# receiver.net
KiCad netlist of a schematic drawn in EAGLE
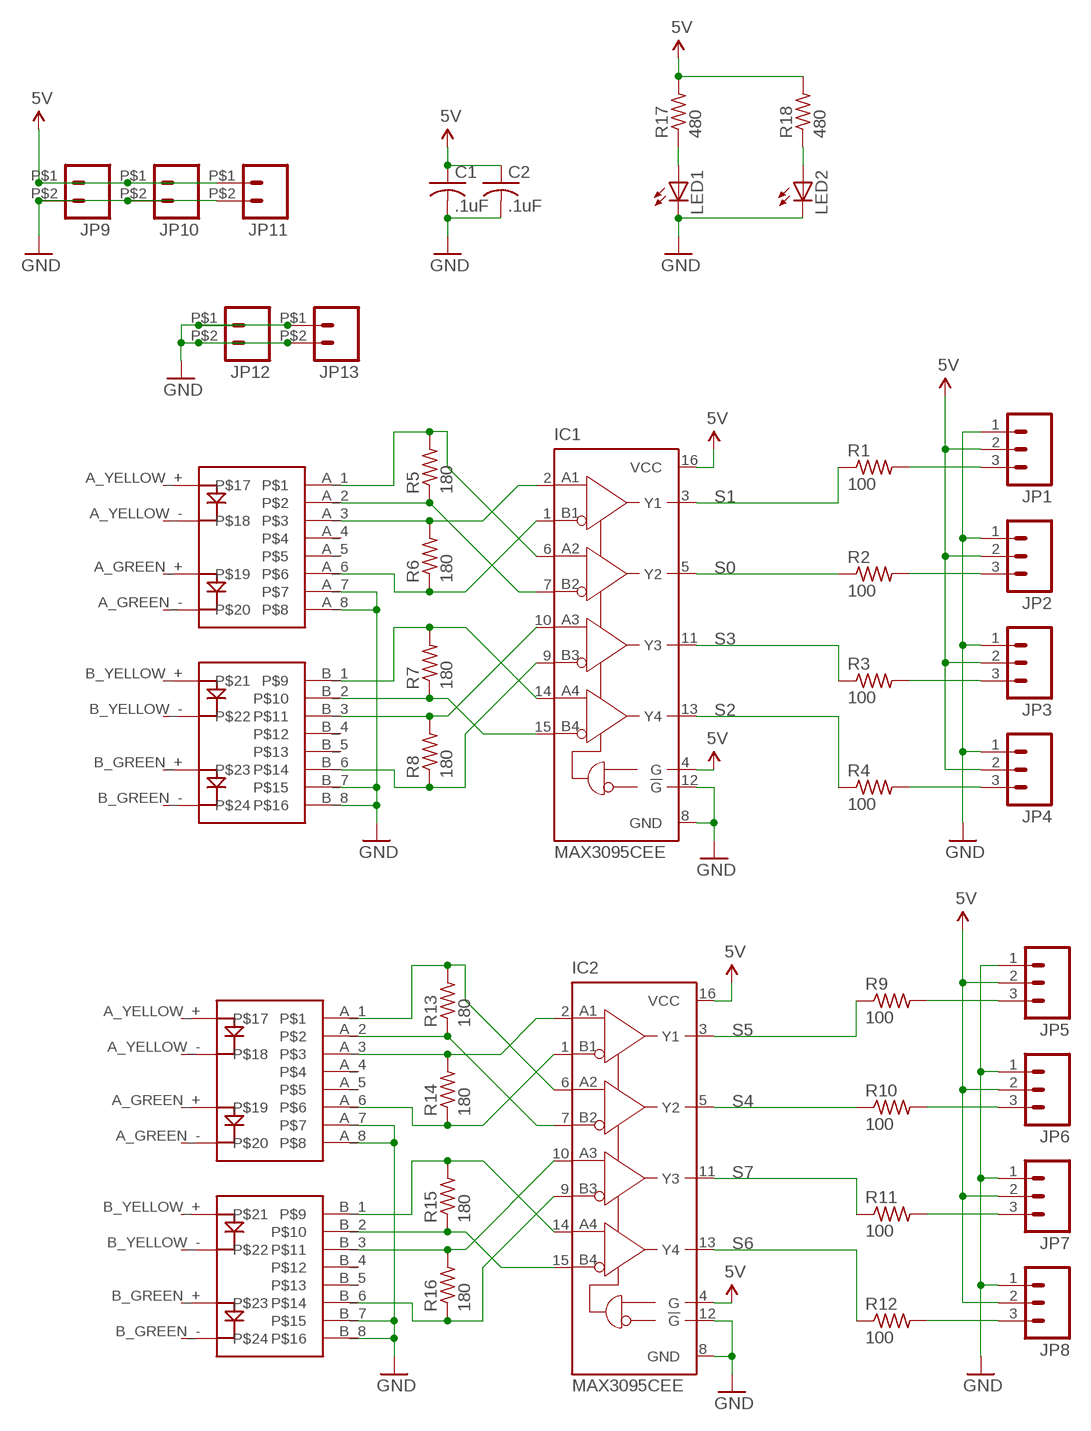
[diagram p0: schematic, sheet 1]

(export (version "E")
  (design (tool "Eeschema 10.0.6"))
  (components
    (comp (ref "C1")
      (value ".1uF")
      (footprint "eagle-import:C0603")
      (libsource (lib "eagle-import") (part "C-USC0603"))
    )
    (comp (ref "C2")
      (value ".1uF")
      (footprint "eagle-import:C0603")
      (libsource (lib "eagle-import") (part "C-USC0603"))
    )
    (comp (ref "IC1")
      (value "MAX3095CEE")
      (footprint "eagle-import:QSOP16")
      (fields (field (name "MPN") "MAX3095CEE+"))
      (libsource (lib "eagle-import") (part "MAX309EE5C"))
    )
    (comp (ref "IC2")
      (value "MAX3095CEE")
      (footprint "eagle-import:QSOP16")
      (fields (field (name "MPN") "MAX3095CEE+"))
      (libsource (lib "eagle-import") (part "MAX309EE5C"))
    )
    (comp (ref "JP1")
      (value "M03-SCREW-5MM")
      (footprint "eagle-import:SCREWTERMINAL-5MM-3")
      (libsource (lib "eagle-import") (part "M03-SCREW-5MM"))
    )
    (comp (ref "JP2")
      (value "M03-SCREW-5MM")
      (footprint "eagle-import:SCREWTERMINAL-5MM-3")
      (libsource (lib "eagle-import") (part "M03-SCREW-5MM"))
    )
    (comp (ref "JP3")
      (value "M03-SCREW-5MM")
      (footprint "eagle-import:SCREWTERMINAL-5MM-3")
      (libsource (lib "eagle-import") (part "M03-SCREW-5MM"))
    )
    (comp (ref "JP4")
      (value "M03-SCREW-5MM")
      (footprint "eagle-import:SCREWTERMINAL-5MM-3")
      (libsource (lib "eagle-import") (part "M03-SCREW-5MM"))
    )
    (comp (ref "JP5")
      (value "M03-SCREW-5MM")
      (footprint "eagle-import:SCREWTERMINAL-5MM-3")
      (libsource (lib "eagle-import") (part "M03-SCREW-5MM"))
    )
    (comp (ref "JP6")
      (value "M03-SCREW-5MM")
      (footprint "eagle-import:SCREWTERMINAL-5MM-3")
      (libsource (lib "eagle-import") (part "M03-SCREW-5MM"))
    )
    (comp (ref "JP7")
      (value "M03-SCREW-5MM")
      (footprint "eagle-import:SCREWTERMINAL-5MM-3")
      (libsource (lib "eagle-import") (part "M03-SCREW-5MM"))
    )
    (comp (ref "JP8")
      (value "M03-SCREW-5MM")
      (footprint "eagle-import:SCREWTERMINAL-5MM-3")
      (libsource (lib "eagle-import") (part "M03-SCREW-5MM"))
    )
    (comp (ref "JP9")
      (value "M026.35MM")
      (footprint "eagle-import:SCREWTERMINAL-6.35MM-2")
      (libsource (lib "eagle-import") (part "M026.35MM"))
    )
    (comp (ref "JP10")
      (value "M026.35MM")
      (footprint "eagle-import:SCREWTERMINAL-6.35MM-2")
      (libsource (lib "eagle-import") (part "M026.35MM"))
    )
    (comp (ref "JP11")
      (value "M026.35MM")
      (footprint "eagle-import:SCREWTERMINAL-6.35MM-2")
      (libsource (lib "eagle-import") (part "M026.35MM"))
    )
    (comp (ref "JP12")
      (value "M026.35MM")
      (footprint "eagle-import:SCREWTERMINAL-6.35MM-2")
      (libsource (lib "eagle-import") (part "M026.35MM"))
    )
    (comp (ref "JP13")
      (value "M026.35MM")
      (footprint "eagle-import:SCREWTERMINAL-6.35MM-2")
      (libsource (lib "eagle-import") (part "M026.35MM"))
    )
    (comp (ref "LED1")
      (value "LEDCHIPLED_0805")
      (footprint "eagle-import:CHIPLED_0805")
      (libsource (lib "eagle-import") (part "LEDCHIPLED_0805"))
    )
    (comp (ref "LED2")
      (value "LEDCHIPLED_0805")
      (footprint "eagle-import:CHIPLED_0805")
      (libsource (lib "eagle-import") (part "LEDCHIPLED_0805"))
    )
    (comp (ref "R1")
      (value "100")
      (footprint "eagle-import:R0603")
      (libsource (lib "eagle-import") (part "R-US_R0603"))
    )
    (comp (ref "R2")
      (value "100")
      (footprint "eagle-import:R0603")
      (libsource (lib "eagle-import") (part "R-US_R0603"))
    )
    (comp (ref "R3")
      (value "100")
      (footprint "eagle-import:R0603")
      (libsource (lib "eagle-import") (part "R-US_R0603"))
    )
    (comp (ref "R4")
      (value "100")
      (footprint "eagle-import:R0603")
      (libsource (lib "eagle-import") (part "R-US_R0603"))
    )
    (comp (ref "R5")
      (value "180")
      (footprint "eagle-import:R0603")
      (libsource (lib "eagle-import") (part "R-US_R0603"))
    )
    (comp (ref "R6")
      (value "180")
      (footprint "eagle-import:R0603")
      (libsource (lib "eagle-import") (part "R-US_R0603"))
    )
    (comp (ref "R7")
      (value "180")
      (footprint "eagle-import:R0603")
      (libsource (lib "eagle-import") (part "R-US_R0603"))
    )
    (comp (ref "R8")
      (value "180")
      (footprint "eagle-import:R0603")
      (libsource (lib "eagle-import") (part "R-US_R0603"))
    )
    (comp (ref "R9")
      (value "100")
      (footprint "eagle-import:R0603")
      (libsource (lib "eagle-import") (part "R-US_R0603"))
    )
    (comp (ref "R10")
      (value "100")
      (footprint "eagle-import:R0603")
      (libsource (lib "eagle-import") (part "R-US_R0603"))
    )
    (comp (ref "R11")
      (value "100")
      (footprint "eagle-import:R0603")
      (libsource (lib "eagle-import") (part "R-US_R0603"))
    )
    (comp (ref "R12")
      (value "100")
      (footprint "eagle-import:R0603")
      (libsource (lib "eagle-import") (part "R-US_R0603"))
    )
    (comp (ref "R13")
      (value "180")
      (footprint "eagle-import:R0603")
      (libsource (lib "eagle-import") (part "R-US_R0603"))
    )
    (comp (ref "R14")
      (value "180")
      (footprint "eagle-import:R0603")
      (libsource (lib "eagle-import") (part "R-US_R0603"))
    )
    (comp (ref "R15")
      (value "180")
      (footprint "eagle-import:R0603")
      (libsource (lib "eagle-import") (part "R-US_R0603"))
    )
    (comp (ref "R16")
      (value "180")
      (footprint "eagle-import:R0603")
      (libsource (lib "eagle-import") (part "R-US_R0603"))
    )
    (comp (ref "R17")
      (value "480")
      (footprint "eagle-import:R0603")
      (libsource (lib "eagle-import") (part "R-US_R0603"))
    )
    (comp (ref "R18")
      (value "480")
      (footprint "eagle-import:R0603")
      (libsource (lib "eagle-import") (part "R-US_R0603"))
    )
    (comp (ref "U$1")
      (value "RJ45_2X1")
      (footprint "eagle-import:RJ45_2X1")
      (libsource (lib "eagle-import") (part "RJ45_2X1"))
    )
    (comp (ref "U$2")
      (value "RJ45_2X1")
      (footprint "eagle-import:RJ45_2X1")
      (libsource (lib "eagle-import") (part "RJ45_2X1"))
    )
  )
  (nets
    (net (code "1") (name "/S0") (class "Default")
      (node (ref "IC1") (pin "5") (pinfunction "Y2_5") (pintype "output"))
      (node (ref "R2") (pin "1") (pinfunction "1_1") (pintype "passive"))
    )
    (net (code "2") (name "/S1") (class "Default")
      (node (ref "IC1") (pin "3") (pinfunction "Y1_3") (pintype "output"))
      (node (ref "R1") (pin "1") (pinfunction "1_1") (pintype "passive"))
    )
    (net (code "3") (name "/S2") (class "Default")
      (node (ref "IC1") (pin "13") (pinfunction "Y4_13") (pintype "output"))
      (node (ref "R4") (pin "1") (pinfunction "1_1") (pintype "passive"))
    )
    (net (code "4") (name "/S3") (class "Default")
      (node (ref "IC1") (pin "11") (pinfunction "Y3_11") (pintype "output"))
      (node (ref "R3") (pin "1") (pinfunction "1_1") (pintype "passive"))
    )
    (net (code "5") (name "/S4") (class "Default")
      (node (ref "IC2") (pin "5") (pinfunction "Y2_5") (pintype "output"))
      (node (ref "R10") (pin "1") (pinfunction "1_1") (pintype "passive"))
    )
    (net (code "6") (name "/S5") (class "Default")
      (node (ref "IC2") (pin "3") (pinfunction "Y1_3") (pintype "output"))
      (node (ref "R9") (pin "1") (pinfunction "1_1") (pintype "passive"))
    )
    (net (code "7") (name "/S6") (class "Default")
      (node (ref "IC2") (pin "13") (pinfunction "Y4_13") (pintype "output"))
      (node (ref "R12") (pin "1") (pinfunction "1_1") (pintype "passive"))
    )
    (net (code "8") (name "/S7") (class "Default")
      (node (ref "IC2") (pin "11") (pinfunction "Y3_11") (pintype "output"))
      (node (ref "R11") (pin "1") (pinfunction "1_1") (pintype "passive"))
    )
    (net (code "9") (name "5V") (class "Default")
      (node (ref "C1") (pin "1") (pinfunction "1_1") (pintype "passive"))
      (node (ref "C2") (pin "1") (pinfunction "1_1") (pintype "passive"))
      (node (ref "IC1") (pin "16") (pinfunction "VCC_16") (pintype "power_in"))
      (node (ref "IC1") (pin "4") (pinfunction "G_4") (pintype "input"))
      (node (ref "IC2") (pin "16") (pinfunction "VCC_16") (pintype "power_in"))
      (node (ref "IC2") (pin "4") (pinfunction "G_4") (pintype "input"))
      (node (ref "JP1") (pin "2") (pinfunction "2_2") (pintype "passive"))
      (node (ref "JP10") (pin "P$1") (pinfunction "1_P$1") (pintype "passive"))
      (node (ref "JP11") (pin "P$1") (pinfunction "1_P$1") (pintype "passive"))
      (node (ref "JP2") (pin "2") (pinfunction "2_2") (pintype "passive"))
      (node (ref "JP3") (pin "2") (pinfunction "2_2") (pintype "passive"))
      (node (ref "JP4") (pin "2") (pinfunction "2_2") (pintype "passive"))
      (node (ref "JP5") (pin "2") (pinfunction "2_2") (pintype "passive"))
      (node (ref "JP6") (pin "2") (pinfunction "2_2") (pintype "passive"))
      (node (ref "JP7") (pin "2") (pinfunction "2_2") (pintype "passive"))
      (node (ref "JP8") (pin "2") (pinfunction "2_2") (pintype "passive"))
      (node (ref "JP9") (pin "P$1") (pinfunction "1_P$1") (pintype "passive"))
      (node (ref "R17") (pin "2") (pinfunction "2_2") (pintype "passive"))
      (node (ref "R18") (pin "2") (pinfunction "2_2") (pintype "passive"))
    )
    (net (code "10") (name "GND") (class "Default")
      (node (ref "C1") (pin "2") (pinfunction "2_2") (pintype "passive"))
      (node (ref "C2") (pin "2") (pinfunction "2_2") (pintype "passive"))
      (node (ref "IC1") (pin "12") (pinfunction "~{G}_12") (pintype "input"))
      (node (ref "IC1") (pin "8") (pinfunction "GND_8") (pintype "power_in"))
      (node (ref "IC2") (pin "12") (pinfunction "~{G}_12") (pintype "input"))
      (node (ref "IC2") (pin "8") (pinfunction "GND_8") (pintype "power_in"))
      (node (ref "JP1") (pin "1") (pinfunction "1_1") (pintype "passive"))
      (node (ref "JP10") (pin "P$2") (pinfunction "2_P$2") (pintype "passive"))
      (node (ref "JP11") (pin "P$2") (pinfunction "2_P$2") (pintype "passive"))
      (node (ref "JP12") (pin "P$1") (pinfunction "1_P$1") (pintype "passive"))
      (node (ref "JP12") (pin "P$2") (pinfunction "2_P$2") (pintype "passive"))
      (node (ref "JP13") (pin "P$1") (pinfunction "1_P$1") (pintype "passive"))
      (node (ref "JP13") (pin "P$2") (pinfunction "2_P$2") (pintype "passive"))
      (node (ref "JP2") (pin "1") (pinfunction "1_1") (pintype "passive"))
      (node (ref "JP3") (pin "1") (pinfunction "1_1") (pintype "passive"))
      (node (ref "JP4") (pin "1") (pinfunction "1_1") (pintype "passive"))
      (node (ref "JP5") (pin "1") (pinfunction "1_1") (pintype "passive"))
      (node (ref "JP6") (pin "1") (pinfunction "1_1") (pintype "passive"))
      (node (ref "JP7") (pin "1") (pinfunction "1_1") (pintype "passive"))
      (node (ref "JP8") (pin "1") (pinfunction "1_1") (pintype "passive"))
      (node (ref "JP9") (pin "P$2") (pinfunction "2_P$2") (pintype "passive"))
      (node (ref "LED1") (pin "C") (pinfunction "C_C") (pintype "passive"))
      (node (ref "LED2") (pin "C") (pinfunction "C_C") (pintype "passive"))
      (node (ref "U$1") (pin "A_7") (pinfunction "P$7_A_7") (pintype "bidirectional"))
      (node (ref "U$1") (pin "A_8") (pinfunction "P$8_A_8") (pintype "bidirectional"))
      (node (ref "U$1") (pin "B_7") (pinfunction "P$15_B_7") (pintype "bidirectional"))
      (node (ref "U$1") (pin "B_8") (pinfunction "P$16_B_8") (pintype "bidirectional"))
      (node (ref "U$2") (pin "A_7") (pinfunction "P$7_A_7") (pintype "bidirectional"))
      (node (ref "U$2") (pin "A_8") (pinfunction "P$8_A_8") (pintype "bidirectional"))
      (node (ref "U$2") (pin "B_7") (pinfunction "P$15_B_7") (pintype "bidirectional"))
      (node (ref "U$2") (pin "B_8") (pinfunction "P$16_B_8") (pintype "bidirectional"))
    )
    (net (code "11") (name "Net-(IC1-A1)") (class "Default")
      (node (ref "IC1") (pin "2") (pinfunction "A1_2") (pintype "input"))
      (node (ref "R6") (pin "2") (pinfunction "2_2") (pintype "passive"))
      (node (ref "U$1") (pin "A_3") (pinfunction "P$3_A_3") (pintype "bidirectional"))
    )
    (net (code "12") (name "Net-(IC1-A2)") (class "Default")
      (node (ref "IC1") (pin "6") (pinfunction "A2_6") (pintype "input"))
      (node (ref "R5") (pin "2") (pinfunction "2_2") (pintype "passive"))
      (node (ref "U$1") (pin "A_1") (pinfunction "P$1_A_1") (pintype "bidirectional"))
    )
    (net (code "13") (name "Net-(IC1-A3)") (class "Default")
      (node (ref "IC1") (pin "10") (pinfunction "A3_10") (pintype "input"))
      (node (ref "R8") (pin "2") (pinfunction "2_2") (pintype "passive"))
      (node (ref "U$1") (pin "B_3") (pinfunction "P$11_B_3") (pintype "bidirectional"))
    )
    (net (code "14") (name "Net-(IC1-A4)") (class "Default")
      (node (ref "IC1") (pin "14") (pinfunction "A4_14") (pintype "input"))
      (node (ref "R7") (pin "2") (pinfunction "2_2") (pintype "passive"))
      (node (ref "U$1") (pin "B_1") (pinfunction "P$9_B_1") (pintype "bidirectional"))
    )
    (net (code "15") (name "Net-(IC1-B1)") (class "Default")
      (node (ref "IC1") (pin "1") (pinfunction "B1_1") (pintype "input"))
      (node (ref "R6") (pin "1") (pinfunction "1_1") (pintype "passive"))
      (node (ref "U$1") (pin "A_6") (pinfunction "P$6_A_6") (pintype "bidirectional"))
    )
    (net (code "16") (name "Net-(IC1-B2)") (class "Default")
      (node (ref "IC1") (pin "7") (pinfunction "B2_7") (pintype "input"))
      (node (ref "R5") (pin "1") (pinfunction "1_1") (pintype "passive"))
      (node (ref "U$1") (pin "A_2") (pinfunction "P$2_A_2") (pintype "bidirectional"))
    )
    (net (code "17") (name "Net-(IC1-B3)") (class "Default")
      (node (ref "IC1") (pin "9") (pinfunction "B3_9") (pintype "input"))
      (node (ref "R8") (pin "1") (pinfunction "1_1") (pintype "passive"))
      (node (ref "U$1") (pin "B_6") (pinfunction "P$14_B_6") (pintype "bidirectional"))
    )
    (net (code "18") (name "Net-(IC1-B4)") (class "Default")
      (node (ref "IC1") (pin "15") (pinfunction "B4_15") (pintype "input"))
      (node (ref "R7") (pin "1") (pinfunction "1_1") (pintype "passive"))
      (node (ref "U$1") (pin "B_2") (pinfunction "P$10_B_2") (pintype "bidirectional"))
    )
    (net (code "19") (name "Net-(IC2-A1)") (class "Default")
      (node (ref "IC2") (pin "2") (pinfunction "A1_2") (pintype "input"))
      (node (ref "R14") (pin "2") (pinfunction "2_2") (pintype "passive"))
      (node (ref "U$2") (pin "A_3") (pinfunction "P$3_A_3") (pintype "bidirectional"))
    )
    (net (code "20") (name "Net-(IC2-A2)") (class "Default")
      (node (ref "IC2") (pin "6") (pinfunction "A2_6") (pintype "input"))
      (node (ref "R13") (pin "2") (pinfunction "2_2") (pintype "passive"))
      (node (ref "U$2") (pin "A_1") (pinfunction "P$1_A_1") (pintype "bidirectional"))
    )
    (net (code "21") (name "Net-(IC2-A3)") (class "Default")
      (node (ref "IC2") (pin "10") (pinfunction "A3_10") (pintype "input"))
      (node (ref "R16") (pin "2") (pinfunction "2_2") (pintype "passive"))
      (node (ref "U$2") (pin "B_3") (pinfunction "P$11_B_3") (pintype "bidirectional"))
    )
    (net (code "22") (name "Net-(IC2-A4)") (class "Default")
      (node (ref "IC2") (pin "14") (pinfunction "A4_14") (pintype "input"))
      (node (ref "R15") (pin "2") (pinfunction "2_2") (pintype "passive"))
      (node (ref "U$2") (pin "B_1") (pinfunction "P$9_B_1") (pintype "bidirectional"))
    )
    (net (code "23") (name "Net-(IC2-B1)") (class "Default")
      (node (ref "IC2") (pin "1") (pinfunction "B1_1") (pintype "input"))
      (node (ref "R14") (pin "1") (pinfunction "1_1") (pintype "passive"))
      (node (ref "U$2") (pin "A_6") (pinfunction "P$6_A_6") (pintype "bidirectional"))
    )
    (net (code "24") (name "Net-(IC2-B2)") (class "Default")
      (node (ref "IC2") (pin "7") (pinfunction "B2_7") (pintype "input"))
      (node (ref "R13") (pin "1") (pinfunction "1_1") (pintype "passive"))
      (node (ref "U$2") (pin "A_2") (pinfunction "P$2_A_2") (pintype "bidirectional"))
    )
    (net (code "25") (name "Net-(IC2-B3)") (class "Default")
      (node (ref "IC2") (pin "9") (pinfunction "B3_9") (pintype "input"))
      (node (ref "R16") (pin "1") (pinfunction "1_1") (pintype "passive"))
      (node (ref "U$2") (pin "B_6") (pinfunction "P$14_B_6") (pintype "bidirectional"))
    )
    (net (code "26") (name "Net-(IC2-B4)") (class "Default")
      (node (ref "IC2") (pin "15") (pinfunction "B4_15") (pintype "input"))
      (node (ref "R15") (pin "1") (pinfunction "1_1") (pintype "passive"))
      (node (ref "U$2") (pin "B_2") (pinfunction "P$10_B_2") (pintype "bidirectional"))
    )
    (net (code "27") (name "Net-(JP1-Pad3)") (class "Default")
      (node (ref "JP1") (pin "3") (pinfunction "3_3") (pintype "passive"))
      (node (ref "R1") (pin "2") (pinfunction "2_2") (pintype "passive"))
    )
    (net (code "28") (name "Net-(JP2-Pad3)") (class "Default")
      (node (ref "JP2") (pin "3") (pinfunction "3_3") (pintype "passive"))
      (node (ref "R2") (pin "2") (pinfunction "2_2") (pintype "passive"))
    )
    (net (code "29") (name "Net-(JP3-Pad3)") (class "Default")
      (node (ref "JP3") (pin "3") (pinfunction "3_3") (pintype "passive"))
      (node (ref "R3") (pin "2") (pinfunction "2_2") (pintype "passive"))
    )
    (net (code "30") (name "Net-(JP4-Pad3)") (class "Default")
      (node (ref "JP4") (pin "3") (pinfunction "3_3") (pintype "passive"))
      (node (ref "R4") (pin "2") (pinfunction "2_2") (pintype "passive"))
    )
    (net (code "31") (name "Net-(JP5-Pad3)") (class "Default")
      (node (ref "JP5") (pin "3") (pinfunction "3_3") (pintype "passive"))
      (node (ref "R9") (pin "2") (pinfunction "2_2") (pintype "passive"))
    )
    (net (code "32") (name "Net-(JP6-Pad3)") (class "Default")
      (node (ref "JP6") (pin "3") (pinfunction "3_3") (pintype "passive"))
      (node (ref "R10") (pin "2") (pinfunction "2_2") (pintype "passive"))
    )
    (net (code "33") (name "Net-(JP7-Pad3)") (class "Default")
      (node (ref "JP7") (pin "3") (pinfunction "3_3") (pintype "passive"))
      (node (ref "R11") (pin "2") (pinfunction "2_2") (pintype "passive"))
    )
    (net (code "34") (name "Net-(JP8-Pad3)") (class "Default")
      (node (ref "JP8") (pin "3") (pinfunction "3_3") (pintype "passive"))
      (node (ref "R12") (pin "2") (pinfunction "2_2") (pintype "passive"))
    )
    (net (code "35") (name "Net-(LED1-PadA)") (class "Default")
      (node (ref "LED1") (pin "A") (pinfunction "A_A") (pintype "passive"))
      (node (ref "R17") (pin "1") (pinfunction "1_1") (pintype "passive"))
    )
    (net (code "36") (name "Net-(LED2-PadA)") (class "Default")
      (node (ref "LED2") (pin "A") (pinfunction "A_A") (pintype "passive"))
      (node (ref "R18") (pin "1") (pinfunction "1_1") (pintype "passive"))
    )
    (net (code "37") (name "unconnected-(U$1-P$4-PadA_4)") (class "Default")
      (node (ref "U$1") (pin "A_4") (pinfunction "P$4_A_4") (pintype "bidirectional"))
    )
    (net (code "38") (name "unconnected-(U$1-P$5-PadA_5)") (class "Default")
      (node (ref "U$1") (pin "A_5") (pinfunction "P$5_A_5") (pintype "bidirectional"))
    )
    (net (code "39") (name "unconnected-(U$1-P$12-PadB_4)") (class "Default")
      (node (ref "U$1") (pin "B_4") (pinfunction "P$12_B_4") (pintype "bidirectional"))
    )
    (net (code "40") (name "unconnected-(U$1-P$13-PadB_5)") (class "Default")
      (node (ref "U$1") (pin "B_5") (pinfunction "P$13_B_5") (pintype "bidirectional"))
    )
    (net (code "41") (name "unconnected-(U$1-P$17-PadA_YELLOW_+)") (class "Default")
      (node (ref "U$1") (pin "A_YELLOW_+") (pinfunction "P$17_A_YELLOW_+") (pintype "bidirectional"))
    )
    (net (code "42") (name "unconnected-(U$1-P$18-PadA_YELLOW_-)") (class "Default")
      (node (ref "U$1") (pin "A_YELLOW_-") (pinfunction "P$18_A_YELLOW_-") (pintype "bidirectional"))
    )
    (net (code "43") (name "unconnected-(U$1-P$19-PadA_GREEN_+)") (class "Default")
      (node (ref "U$1") (pin "A_GREEN_+") (pinfunction "P$19_A_GREEN_+") (pintype "bidirectional"))
    )
    (net (code "44") (name "unconnected-(U$1-P$20-PadA_GREEN_-)") (class "Default")
      (node (ref "U$1") (pin "A_GREEN_-") (pinfunction "P$20_A_GREEN_-") (pintype "bidirectional"))
    )
    (net (code "45") (name "unconnected-(U$1-P$21-PadB_YELLOW_+)") (class "Default")
      (node (ref "U$1") (pin "B_YELLOW_+") (pinfunction "P$21_B_YELLOW_+") (pintype "bidirectional"))
    )
    (net (code "46") (name "unconnected-(U$1-P$22-PadB_YELLOW_-)") (class "Default")
      (node (ref "U$1") (pin "B_YELLOW_-") (pinfunction "P$22_B_YELLOW_-") (pintype "bidirectional"))
    )
    (net (code "47") (name "unconnected-(U$1-P$23-PadB_GREEN_+)") (class "Default")
      (node (ref "U$1") (pin "B_GREEN_+") (pinfunction "P$23_B_GREEN_+") (pintype "bidirectional"))
    )
    (net (code "48") (name "unconnected-(U$1-P$24-PadB_GREEN_-)") (class "Default")
      (node (ref "U$1") (pin "B_GREEN_-") (pinfunction "P$24_B_GREEN_-") (pintype "bidirectional"))
    )
    (net (code "49") (name "unconnected-(U$2-P$4-PadA_4)") (class "Default")
      (node (ref "U$2") (pin "A_4") (pinfunction "P$4_A_4") (pintype "bidirectional"))
    )
    (net (code "50") (name "unconnected-(U$2-P$5-PadA_5)") (class "Default")
      (node (ref "U$2") (pin "A_5") (pinfunction "P$5_A_5") (pintype "bidirectional"))
    )
    (net (code "51") (name "unconnected-(U$2-P$12-PadB_4)") (class "Default")
      (node (ref "U$2") (pin "B_4") (pinfunction "P$12_B_4") (pintype "bidirectional"))
    )
    (net (code "52") (name "unconnected-(U$2-P$13-PadB_5)") (class "Default")
      (node (ref "U$2") (pin "B_5") (pinfunction "P$13_B_5") (pintype "bidirectional"))
    )
    (net (code "53") (name "unconnected-(U$2-P$17-PadA_YELLOW_+)") (class "Default")
      (node (ref "U$2") (pin "A_YELLOW_+") (pinfunction "P$17_A_YELLOW_+") (pintype "bidirectional"))
    )
    (net (code "54") (name "unconnected-(U$2-P$18-PadA_YELLOW_-)") (class "Default")
      (node (ref "U$2") (pin "A_YELLOW_-") (pinfunction "P$18_A_YELLOW_-") (pintype "bidirectional"))
    )
    (net (code "55") (name "unconnected-(U$2-P$19-PadA_GREEN_+)") (class "Default")
      (node (ref "U$2") (pin "A_GREEN_+") (pinfunction "P$19_A_GREEN_+") (pintype "bidirectional"))
    )
    (net (code "56") (name "unconnected-(U$2-P$20-PadA_GREEN_-)") (class "Default")
      (node (ref "U$2") (pin "A_GREEN_-") (pinfunction "P$20_A_GREEN_-") (pintype "bidirectional"))
    )
    (net (code "57") (name "unconnected-(U$2-P$21-PadB_YELLOW_+)") (class "Default")
      (node (ref "U$2") (pin "B_YELLOW_+") (pinfunction "P$21_B_YELLOW_+") (pintype "bidirectional"))
    )
    (net (code "58") (name "unconnected-(U$2-P$22-PadB_YELLOW_-)") (class "Default")
      (node (ref "U$2") (pin "B_YELLOW_-") (pinfunction "P$22_B_YELLOW_-") (pintype "bidirectional"))
    )
    (net (code "59") (name "unconnected-(U$2-P$23-PadB_GREEN_+)") (class "Default")
      (node (ref "U$2") (pin "B_GREEN_+") (pinfunction "P$23_B_GREEN_+") (pintype "bidirectional"))
    )
    (net (code "60") (name "unconnected-(U$2-P$24-PadB_GREEN_-)") (class "Default")
      (node (ref "U$2") (pin "B_GREEN_-") (pinfunction "P$24_B_GREEN_-") (pintype "bidirectional"))
    )
  )
)
